# SchemaCircuito5Sensori.net
KiCad netlist of a schematic drawn in EAGLE
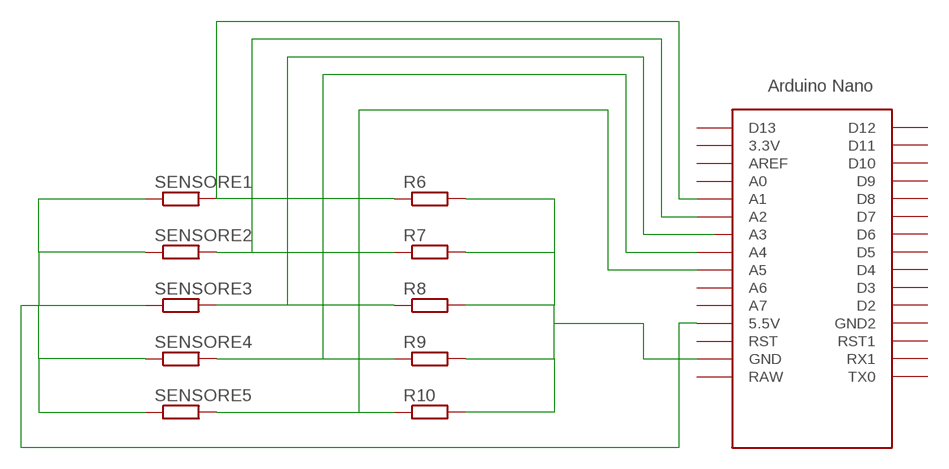
[diagram p0: schematic, sheet 1]

(export (version "E")
  (design (tool "Eeschema 10.0.6"))
  (components
    (comp (ref "R6")
      (value "R-EU_0207/10")
      (footprint "eagle-import:0207_10")
      (libsource (lib "eagle-import") (part "R-EU_0207/10"))
    )
    (comp (ref "R7")
      (value "R-EU_0207/10")
      (footprint "eagle-import:0207_10")
      (libsource (lib "eagle-import") (part "R-EU_0207/10"))
    )
    (comp (ref "R8")
      (value "R-EU_0207/10")
      (footprint "eagle-import:0207_10")
      (libsource (lib "eagle-import") (part "R-EU_0207/10"))
    )
    (comp (ref "R9")
      (value "R-EU_0207/10")
      (footprint "eagle-import:0207_10")
      (libsource (lib "eagle-import") (part "R-EU_0207/10"))
    )
    (comp (ref "R10")
      (value "R-EU_0207/10")
      (footprint "eagle-import:0207_10")
      (libsource (lib "eagle-import") (part "R-EU_0207/10"))
    )
    (comp (ref "SENSORE1")
      (value "R-EU_0207/10")
      (footprint "eagle-import:0207_10")
      (libsource (lib "eagle-import") (part "R-EU_0207/10"))
    )
    (comp (ref "SENSORE2")
      (value "R-EU_0207/10")
      (footprint "eagle-import:0207_10")
      (libsource (lib "eagle-import") (part "R-EU_0207/10"))
    )
    (comp (ref "SENSORE3")
      (value "R-EU_0207/10")
      (footprint "eagle-import:0207_10")
      (libsource (lib "eagle-import") (part "R-EU_0207/10"))
    )
    (comp (ref "SENSORE4")
      (value "R-EU_0207/10")
      (footprint "eagle-import:0207_10")
      (libsource (lib "eagle-import") (part "R-EU_0207/10"))
    )
    (comp (ref "SENSORE5")
      (value "R-EU_0207/10")
      (footprint "eagle-import:0207_10")
      (libsource (lib "eagle-import") (part "R-EU_0207/10"))
    )
    (comp (ref "U$1")
      (value "NANO")
      (footprint "eagle-import:NANO")
      (libsource (lib "eagle-import") (part "NANO"))
    )
  )
  (nets
    (net (code "1") (name "Net-(R6-Pad1)") (class "Default")
      (node (ref "R6") (pin "1") (pinfunction "1_1") (pintype "passive"))
      (node (ref "SENSORE1") (pin "2") (pinfunction "2_2") (pintype "passive"))
      (node (ref "U$1") (pin "A1") (pinfunction "A1_A1") (pintype "bidirectional"))
    )
    (net (code "2") (name "Net-(R7-Pad1)") (class "Default")
      (node (ref "R7") (pin "1") (pinfunction "1_1") (pintype "passive"))
      (node (ref "SENSORE2") (pin "2") (pinfunction "2_2") (pintype "passive"))
      (node (ref "U$1") (pin "A2") (pinfunction "A2_A2") (pintype "bidirectional"))
    )
    (net (code "3") (name "Net-(R8-Pad1)") (class "Default")
      (node (ref "R8") (pin "1") (pinfunction "1_1") (pintype "passive"))
      (node (ref "SENSORE3") (pin "2") (pinfunction "2_2") (pintype "passive"))
      (node (ref "U$1") (pin "A3") (pinfunction "A3_A3") (pintype "bidirectional"))
    )
    (net (code "4") (name "Net-(R9-Pad1)") (class "Default")
      (node (ref "R9") (pin "1") (pinfunction "1_1") (pintype "passive"))
      (node (ref "SENSORE4") (pin "2") (pinfunction "2_2") (pintype "passive"))
      (node (ref "U$1") (pin "A4") (pinfunction "A4_A4") (pintype "bidirectional"))
    )
    (net (code "5") (name "Net-(R10-Pad1)") (class "Default")
      (node (ref "R10") (pin "1") (pinfunction "1_1") (pintype "passive"))
      (node (ref "SENSORE5") (pin "2") (pinfunction "2_2") (pintype "passive"))
    )
    (net (code "6") (name "Net-(R10-Pad2)") (class "Default")
      (node (ref "R10") (pin "2") (pinfunction "2_2") (pintype "passive"))
      (node (ref "R6") (pin "2") (pinfunction "2_2") (pintype "passive"))
      (node (ref "R7") (pin "2") (pinfunction "2_2") (pintype "passive"))
      (node (ref "R8") (pin "2") (pinfunction "2_2") (pintype "passive"))
      (node (ref "R9") (pin "2") (pinfunction "2_2") (pintype "passive"))
      (node (ref "U$1") (pin "GND") (pinfunction "GND_GND") (pintype "bidirectional"))
    )
    (net (code "7") (name "Net-(U$1-5.5V)") (class "Default")
      (node (ref "SENSORE1") (pin "1") (pinfunction "1_1") (pintype "passive"))
      (node (ref "SENSORE2") (pin "1") (pinfunction "1_1") (pintype "passive"))
      (node (ref "SENSORE3") (pin "1") (pinfunction "1_1") (pintype "passive"))
      (node (ref "SENSORE4") (pin "1") (pinfunction "1_1") (pintype "passive"))
      (node (ref "SENSORE5") (pin "1") (pinfunction "1_1") (pintype "passive"))
      (node (ref "U$1") (pin "5V") (pinfunction "5.5V_5V") (pintype "bidirectional"))
    )
    (net (code "8") (name "unconnected-(U$1-GND2-PadGND1)") (class "Default")
      (node (ref "U$1") (pin "GND1") (pinfunction "GND2_GND1") (pintype "bidirectional"))
    )
    (net (code "9") (name "unconnected-(U$1-Pad3.3V)") (class "Default")
      (node (ref "U$1") (pin "3.3V") (pinfunction "3.3V_3.3V") (pintype "bidirectional"))
    )
    (net (code "10") (name "unconnected-(U$1-PadA0)") (class "Default")
      (node (ref "U$1") (pin "A0") (pinfunction "A0_A0") (pintype "bidirectional"))
    )
    (net (code "11") (name "unconnected-(U$1-PadA5)") (class "Default")
      (node (ref "U$1") (pin "A5") (pinfunction "A5_A5") (pintype "bidirectional"))
    )
    (net (code "12") (name "unconnected-(U$1-PadA6)") (class "Default")
      (node (ref "U$1") (pin "A6") (pinfunction "A6_A6") (pintype "bidirectional"))
    )
    (net (code "13") (name "unconnected-(U$1-PadA7)") (class "Default")
      (node (ref "U$1") (pin "A7") (pinfunction "A7_A7") (pintype "bidirectional"))
    )
    (net (code "14") (name "unconnected-(U$1-PadAREF)") (class "Default")
      (node (ref "U$1") (pin "AREF") (pinfunction "AREF_AREF") (pintype "bidirectional"))
    )
    (net (code "15") (name "unconnected-(U$1-PadD2)") (class "Default")
      (node (ref "U$1") (pin "D2") (pinfunction "D2_D2") (pintype "bidirectional"))
    )
    (net (code "16") (name "unconnected-(U$1-PadD3)") (class "Default")
      (node (ref "U$1") (pin "D3") (pinfunction "D3_D3") (pintype "bidirectional"))
    )
    (net (code "17") (name "unconnected-(U$1-PadD4)") (class "Default")
      (node (ref "U$1") (pin "D4") (pinfunction "D4_D4") (pintype "bidirectional"))
    )
    (net (code "18") (name "unconnected-(U$1-PadD5)") (class "Default")
      (node (ref "U$1") (pin "D5") (pinfunction "D5_D5") (pintype "bidirectional"))
    )
    (net (code "19") (name "unconnected-(U$1-PadD6)") (class "Default")
      (node (ref "U$1") (pin "D6") (pinfunction "D6_D6") (pintype "bidirectional"))
    )
    (net (code "20") (name "unconnected-(U$1-PadD7)") (class "Default")
      (node (ref "U$1") (pin "D7") (pinfunction "D7_D7") (pintype "bidirectional"))
    )
    (net (code "21") (name "unconnected-(U$1-PadD8)") (class "Default")
      (node (ref "U$1") (pin "D8") (pinfunction "D8_D8") (pintype "bidirectional"))
    )
    (net (code "22") (name "unconnected-(U$1-PadD9)") (class "Default")
      (node (ref "U$1") (pin "D9") (pinfunction "D9_D9") (pintype "bidirectional"))
    )
    (net (code "23") (name "unconnected-(U$1-PadD10)") (class "Default")
      (node (ref "U$1") (pin "D10") (pinfunction "D10_D10") (pintype "bidirectional"))
    )
    (net (code "24") (name "unconnected-(U$1-PadD11)") (class "Default")
      (node (ref "U$1") (pin "D11") (pinfunction "D11_D11") (pintype "bidirectional"))
    )
    (net (code "25") (name "unconnected-(U$1-PadD12)") (class "Default")
      (node (ref "U$1") (pin "D12") (pinfunction "D12_D12") (pintype "bidirectional"))
    )
    (net (code "26") (name "unconnected-(U$1-PadD13)") (class "Default")
      (node (ref "U$1") (pin "D13") (pinfunction "D13_D13") (pintype "bidirectional"))
    )
    (net (code "27") (name "unconnected-(U$1-PadICSP1)") (class "Default")
      (node (ref "U$1") (pin "ICSP1") (pinfunction "ICSP1_ICSP1") (pintype "bidirectional"))
    )
    (net (code "28") (name "unconnected-(U$1-PadICSP2)") (class "Default")
      (node (ref "U$1") (pin "ICSP2") (pinfunction "ICSP2_ICSP2") (pintype "bidirectional"))
    )
    (net (code "29") (name "unconnected-(U$1-PadICSP3)") (class "Default")
      (node (ref "U$1") (pin "ICSP3") (pinfunction "ICSP3_ICSP3") (pintype "bidirectional"))
    )
    (net (code "30") (name "unconnected-(U$1-PadICSP4)") (class "Default")
      (node (ref "U$1") (pin "ICSP4") (pinfunction "ICSP4_ICSP4") (pintype "bidirectional"))
    )
    (net (code "31") (name "unconnected-(U$1-PadICSP5)") (class "Default")
      (node (ref "U$1") (pin "ICSP5") (pinfunction "ICSP5_ICSP5") (pintype "bidirectional"))
    )
    (net (code "32") (name "unconnected-(U$1-PadICSP6)") (class "Default")
      (node (ref "U$1") (pin "ICSP6") (pinfunction "ICSP6_ICSP6") (pintype "bidirectional"))
    )
    (net (code "33") (name "unconnected-(U$1-PadRAW)") (class "Default")
      (node (ref "U$1") (pin "RAW") (pinfunction "RAW_RAW") (pintype "bidirectional"))
    )
    (net (code "34") (name "unconnected-(U$1-PadRST)") (class "Default")
      (node (ref "U$1") (pin "RST") (pinfunction "RST_RST") (pintype "bidirectional"))
    )
    (net (code "35") (name "unconnected-(U$1-PadRST1)") (class "Default")
      (node (ref "U$1") (pin "RST1") (pinfunction "RST1_RST1") (pintype "bidirectional"))
    )
    (net (code "36") (name "unconnected-(U$1-PadRX1)") (class "Default")
      (node (ref "U$1") (pin "RX1") (pinfunction "RX1_RX1") (pintype "bidirectional"))
    )
    (net (code "37") (name "unconnected-(U$1-PadTX0)") (class "Default")
      (node (ref "U$1") (pin "TX0") (pinfunction "TX0_TX0") (pintype "bidirectional"))
    )
  )
)
